# acc.net
KiCad netlist of a schematic drawn in Altium Designer
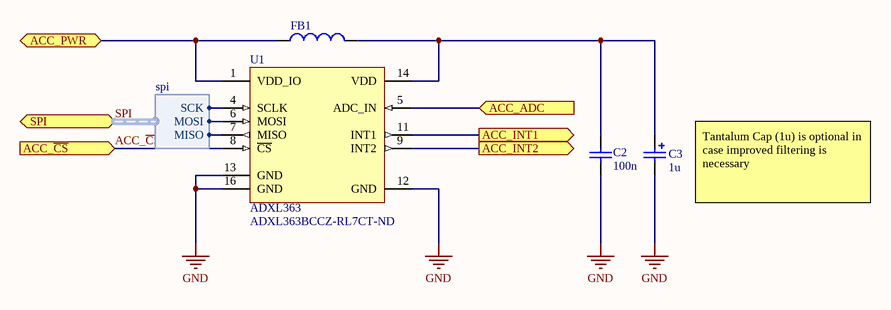
[diagram p0: acc.SchDoc]

(export (version "E")
  (design (tool "Eeschema 10.0.6"))
  (components
    (comp (ref "C2")
      (value "100n")
      (footprint "CAPC1608X95N")
      (description "Capacitor")
      (fields (field (name "VOLTAGE") "16V"))
      (libsource (lib "rlc") (part "C"))
    )
    (comp (ref "C3")
      (value "1u")
      (footprint "CAPC1608X95N_POL")
      (description "Polarized Capacitor (Surface Mount)")
      (fields (field (name "VOLTAGE") "16V"))
      (libsource (lib "rlc") (part "CPOL"))
    )
    (comp (ref "FB1")
      (value "~")
      (footprint "RESC1608X55N")
      (description "Ferrite Bead")
      (libsource (lib "rlc") (part "FB"))
    )
    (comp (ref "U1")
      (value "ADXL363")
      (footprint "LGA_ADXL363")
      (description "Micropower 3-Sensor Combination  Including Acceleration and Temperature")
      (fields (field (name "SUPPLIER PART NUMBER 1") "ADXL363BCCZ-RL7CT-ND"))
      (libsource (lib "sensor") (part "ADXL363"))
    )
  )
  (nets
    (net (code "2") (name "/ACC_ADC") (class "Default")
      (node (ref "U1") (pin "5") (pinfunction "ADC_IN_5") (pintype "input"))
    )
    (net (code "3") (name "/ACC_INT1") (class "Default")
      (node (ref "U1") (pin "11") (pinfunction "INT1_11") (pintype "output"))
    )
    (net (code "4") (name "/ACC_INT2") (class "Default")
      (node (ref "U1") (pin "9") (pinfunction "INT2_9") (pintype "output"))
    )
    (net (code "5") (name "/ACC_PWR") (class "Default")
      (node (ref "FB1") (pin "1") (pinfunction "1_1") (pintype "passive"))
      (node (ref "U1") (pin "1") (pinfunction "VDD_IO_1") (pintype "passive"))
    )
    (net (code "6") (name "/ACC_~{CS}") (class "Default")
      (node (ref "U1") (pin "8") (pinfunction "~{CS}_8") (pintype "input"))
    )
    (net (code "7") (name "/MISO") (class "Default")
      (node (ref "U1") (pin "7") (pinfunction "MISO_7") (pintype "output"))
    )
    (net (code "8") (name "/MOSI") (class "Default")
      (node (ref "U1") (pin "6") (pinfunction "MOSI_6") (pintype "input"))
    )
    (net (code "9") (name "/SCK") (class "Default")
      (node (ref "U1") (pin "4") (pinfunction "SCLK_4") (pintype "input"))
    )
    (net (code "11") (name "GND") (class "Default")
      (node (ref "C2") (pin "1") (pinfunction "1_1") (pintype "passive"))
      (node (ref "C3") (pin "2") (pinfunction "2_2") (pintype "passive"))
      (node (ref "U1") (pin "12") (pinfunction "GND_12") (pintype "passive"))
      (node (ref "U1") (pin "13") (pinfunction "GND_13") (pintype "passive"))
      (node (ref "U1") (pin "16") (pinfunction "GND_16") (pintype "passive"))
    )
    (net (code "12") (name "Net-(U1-VDD)") (class "Default")
      (node (ref "C2") (pin "2") (pinfunction "2_2") (pintype "passive"))
      (node (ref "C3") (pin "1") (pinfunction "1_1") (pintype "passive"))
      (node (ref "FB1") (pin "2") (pinfunction "2_2") (pintype "passive"))
      (node (ref "U1") (pin "14") (pinfunction "VDD_14") (pintype "passive"))
    )
    (net (code "13") (name "unconnected-(U1-NC-Pad2)") (class "Default")
      (node (ref "U1") (pin "2") (pinfunction "NC_2") (pintype "passive"))
    )
    (net (code "14") (name "unconnected-(U1-NC-Pad15)") (class "Default")
      (node (ref "U1") (pin "15") (pinfunction "NC_15") (pintype "passive"))
    )
    (net (code "15") (name "unconnected-(U1-RES-Pad3)") (class "Default")
      (node (ref "U1") (pin "3") (pinfunction "RES_3") (pintype "passive"))
    )
    (net (code "16") (name "unconnected-(U1-RES-Pad10)") (class "Default")
      (node (ref "U1") (pin "10") (pinfunction "RES_10") (pintype "passive"))
    )
  )
)
